# IoT_Shield_v1_0.net
KiCad netlist of a schematic drawn in EAGLE
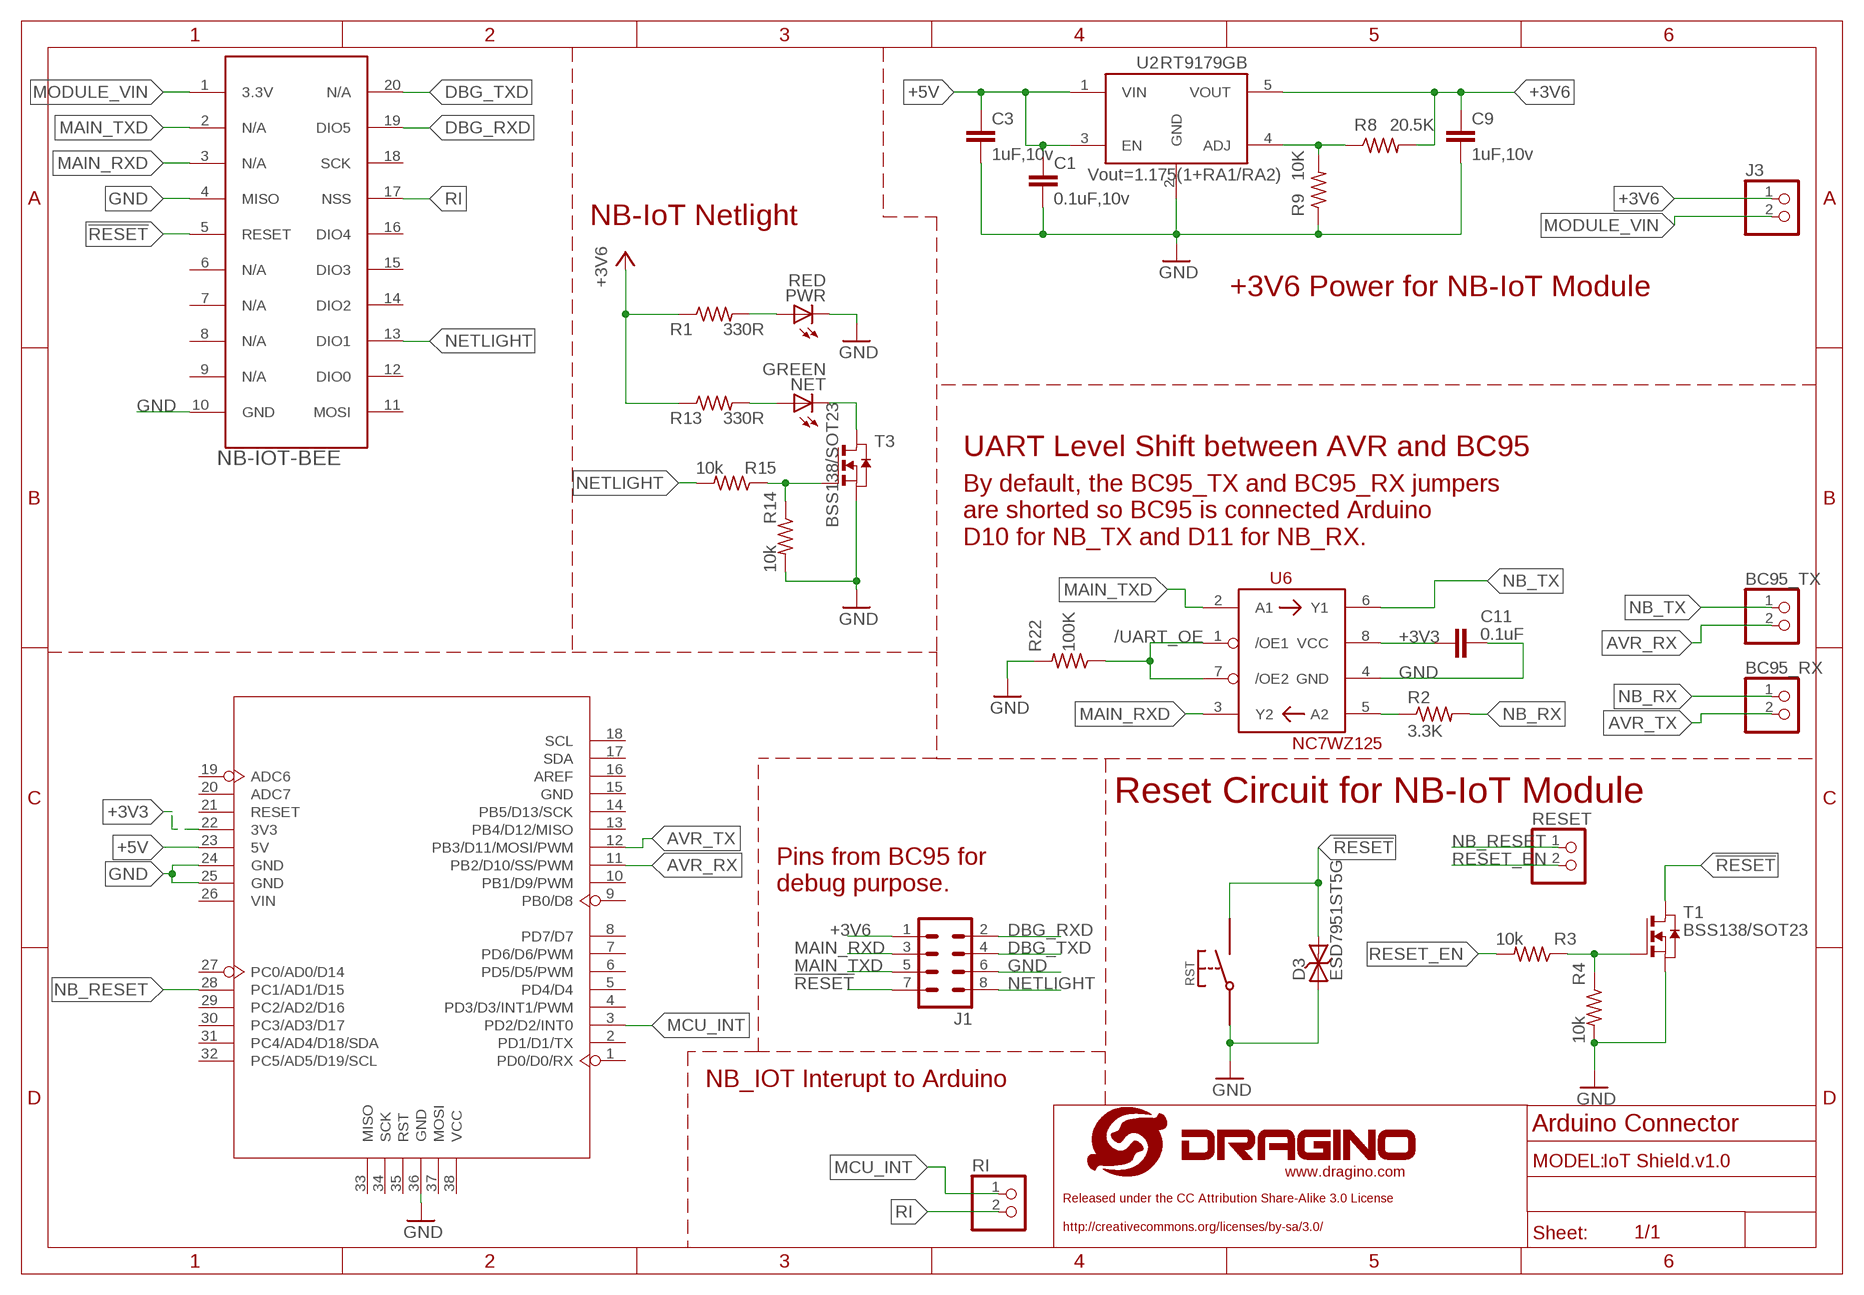
[diagram p0: schematic, sheet 1]

(export (version "E")
  (design (tool "Eeschema 10.0.6"))
  (components
    (comp (ref "BC95_RX")
      (value "PINHD-1X2")
      (footprint "eagle-import:1X02")
      (libsource (lib "eagle-import") (part "PINHD-1X2"))
    )
    (comp (ref "BC95_TX")
      (value "PINHD-1X2")
      (footprint "eagle-import:1X02")
      (libsource (lib "eagle-import") (part "PINHD-1X2"))
    )
    (comp (ref "C1")
      (value "0.1uF,10v")
      (footprint "eagle-import:C0402")
      (libsource (lib "eagle-import") (part "C-EUC0402"))
    )
    (comp (ref "C3")
      (value "1uF,10v")
      (footprint "eagle-import:C0402")
      (libsource (lib "eagle-import") (part "C-EUC0402"))
    )
    (comp (ref "C9")
      (value "1uF,10v")
      (footprint "eagle-import:C0402")
      (libsource (lib "eagle-import") (part "C-EUC0402"))
    )
    (comp (ref "C11")
      (value "0.1uF")
      (footprint "eagle-import:C0402")
      (libsource (lib "eagle-import") (part "C-EUC0402"))
    )
    (comp (ref "D3")
      (value "ESD7951ST5G")
      (footprint "eagle-import:SOD−923")
      (libsource (lib "eagle-import") (part "TVSSOD−923"))
    )
    (comp (ref "IOT-BEE")
      (value "NB-IOT-BEE")
      (footprint "eagle-import:LORA")
      (libsource (lib "eagle-import") (part "LORAHAT_S"))
    )
    (comp (ref "J1")
      (value "MA04-2")
      (footprint "eagle-import:MA04-2")
      (libsource (lib "eagle-import") (part "MA04-2"))
    )
    (comp (ref "J3")
      (value "PINHD-1X2")
      (footprint "eagle-import:1X02")
      (libsource (lib "eagle-import") (part "PINHD-1X2"))
    )
    (comp (ref "NET")
      (value "GREEN")
      (footprint "eagle-import:CHIP-LED0603")
      (libsource (lib "eagle-import") (part "LEDCHIP-LED0603"))
    )
    (comp (ref "PWR")
      (value "RED")
      (footprint "eagle-import:CHIP-LED0603")
      (libsource (lib "eagle-import") (part "LEDCHIP-LED0603"))
    )
    (comp (ref "R1")
      (value "330R")
      (footprint "eagle-import:R0402")
      (libsource (lib "eagle-import") (part "R-US_R0402"))
    )
    (comp (ref "R2")
      (value "3.3K")
      (footprint "eagle-import:R0402")
      (libsource (lib "eagle-import") (part "R-US_R0402"))
    )
    (comp (ref "R3")
      (value "10k")
      (footprint "eagle-import:R0402")
      (libsource (lib "eagle-import") (part "R-US_R0402"))
    )
    (comp (ref "R4")
      (value "10k")
      (footprint "eagle-import:R0402")
      (libsource (lib "eagle-import") (part "R-US_R0402"))
    )
    (comp (ref "R8")
      (value "20.5K")
      (footprint "eagle-import:R0402")
      (libsource (lib "eagle-import") (part "R-US_R0402"))
    )
    (comp (ref "R9")
      (value "10K")
      (footprint "eagle-import:R0402")
      (libsource (lib "eagle-import") (part "R-US_R0402"))
    )
    (comp (ref "R13")
      (value "330R")
      (footprint "eagle-import:R0402")
      (libsource (lib "eagle-import") (part "R-US_R0402"))
    )
    (comp (ref "R14")
      (value "10k")
      (footprint "eagle-import:R0402")
      (libsource (lib "eagle-import") (part "R-US_R0402"))
    )
    (comp (ref "R15")
      (value "10k")
      (footprint "eagle-import:R0402")
      (libsource (lib "eagle-import") (part "R-US_R0402"))
    )
    (comp (ref "R22")
      (value "100K")
      (footprint "eagle-import:R0402")
      (libsource (lib "eagle-import") (part "R-US_R0402"))
    )
    (comp (ref "RESET")
      (value "PINHD-1X2")
      (footprint "eagle-import:1X02")
      (libsource (lib "eagle-import") (part "PINHD-1X2"))
    )
    (comp (ref "RI")
      (value "PINHD-1X2")
      (footprint "eagle-import:1X02")
      (libsource (lib "eagle-import") (part "PINHD-1X2"))
    )
    (comp (ref "RST")
      (value "SWITCHTS-017")
      (footprint "eagle-import:TS-017")
      (libsource (lib "eagle-import") (part "SWITCHTS-017"))
    )
    (comp (ref "T1")
      (value "BSS138/SOT23")
      (footprint "eagle-import:SOT-23")
      (libsource (lib "eagle-import") (part "NMOSFET-SOT23"))
    )
    (comp (ref "T3")
      (value "BSS138/SOT23")
      (footprint "eagle-import:SOT-23")
      (libsource (lib "eagle-import") (part "NMOSFET-SOT23"))
    )
    (comp (ref "U$1")
      (value "LOGO-NEW")
      (footprint "eagle-import:LOGO-SILK-NEW")
      (libsource (lib "eagle-import") (part "LOGO-NEW"))
    )
    (comp (ref "U2")
      (value "RT9179GB")
      (footprint "eagle-import:SOT23-5")
      (libsource (lib "eagle-import") (part "RT9179"))
    )
    (comp (ref "U5")
      (value "MOUDLE_ARDUINO-38PMOUDLE_ARDUINO-38P_L")
      (footprint "eagle-import:MOUDLE_ARDUINO-38P_L")
      (libsource (lib "eagle-import") (part "MOUDLE_ARDUINO-38PMOUDLE_ARDUINO-38P_L"))
    )
    (comp (ref "U6")
      (value "NC7WZ125")
      (footprint "eagle-import:US8")
      (libsource (lib "eagle-import") (part "NC7WZ125"))
    )
  )
  (nets
    (net (code "1") (name "+3V3") (class "Default")
      (node (ref "C11") (pin "2") (pinfunction "2_2") (pintype "passive"))
      (node (ref "U5") (pin "22") (pinfunction "3V3_22") (pintype "bidirectional"))
      (node (ref "U6") (pin "8") (pinfunction "VCC_8") (pintype "power_in"))
    )
    (net (code "2") (name "+3V6") (class "Default")
      (node (ref "C9") (pin "1") (pinfunction "1_1") (pintype "passive"))
      (node (ref "J1") (pin "1") (pinfunction "1_1") (pintype "passive"))
      (node (ref "J3") (pin "1") (pinfunction "1_1") (pintype "passive"))
      (node (ref "R1") (pin "1") (pinfunction "1_1") (pintype "passive"))
      (node (ref "R13") (pin "1") (pinfunction "1_1") (pintype "passive"))
      (node (ref "R8") (pin "2") (pinfunction "2_2") (pintype "passive"))
      (node (ref "U2") (pin "5") (pinfunction "VOUT_5") (pintype "bidirectional"))
    )
    (net (code "3") (name "+5V") (class "Default")
      (node (ref "C1") (pin "1") (pinfunction "1_1") (pintype "passive"))
      (node (ref "C3") (pin "1") (pinfunction "1_1") (pintype "passive"))
      (node (ref "U2") (pin "1") (pinfunction "VIN_1") (pintype "bidirectional"))
      (node (ref "U2") (pin "3") (pinfunction "EN_3") (pintype "bidirectional"))
      (node (ref "U5") (pin "23") (pinfunction "5V_23") (pintype "bidirectional"))
    )
    (net (code "4") (name "/{slash}UART_OE") (class "Default")
      (node (ref "R22") (pin "1") (pinfunction "1_1") (pintype "passive"))
      (node (ref "U6") (pin "1") (pinfunction "/OE1_1") (pintype "input"))
      (node (ref "U6") (pin "7") (pinfunction "/OE2_7") (pintype "input"))
    )
    (net (code "5") (name "/~{RESET}") (class "Default")
      (node (ref "D3") (pin "P$2") (pinfunction "2_P$2") (pintype "passive"))
      (node (ref "IOT-BEE") (pin "5") (pinfunction "RESET_5") (pintype "bidirectional"))
      (node (ref "J1") (pin "7") (pinfunction "7_7") (pintype "passive"))
      (node (ref "RST") (pin "P$2") (pinfunction "P$2_P$2") (pintype "bidirectional"))
      (node (ref "T1") (pin "1") (pinfunction "D_1") (pintype "passive"))
    )
    (net (code "6") (name "AVR_RX") (class "Default")
      (node (ref "BC95_TX") (pin "2") (pinfunction "2_2") (pintype "passive"))
      (node (ref "U5") (pin "11") (pinfunction "PB2/D10/SS/PWM_11") (pintype "bidirectional"))
    )
    (net (code "7") (name "AVR_TX") (class "Default")
      (node (ref "BC95_RX") (pin "2") (pinfunction "2_2") (pintype "passive"))
      (node (ref "U5") (pin "12") (pinfunction "PB3/D11/MOSI/PWM_12") (pintype "bidirectional"))
    )
    (net (code "8") (name "DBG_RXD") (class "Default")
      (node (ref "IOT-BEE") (pin "19") (pinfunction "DIO5_19") (pintype "bidirectional"))
      (node (ref "J1") (pin "2") (pinfunction "2_2") (pintype "passive"))
    )
    (net (code "9") (name "DBG_TXD") (class "Default")
      (node (ref "IOT-BEE") (pin "20") (pinfunction "N/A_20") (pintype "bidirectional"))
      (node (ref "J1") (pin "4") (pinfunction "4_4") (pintype "passive"))
    )
    (net (code "10") (name "GND") (class "Default")
      (node (ref "C1") (pin "2") (pinfunction "2_2") (pintype "passive"))
      (node (ref "C11") (pin "1") (pinfunction "1_1") (pintype "passive"))
      (node (ref "C3") (pin "2") (pinfunction "2_2") (pintype "passive"))
      (node (ref "C9") (pin "2") (pinfunction "2_2") (pintype "passive"))
      (node (ref "D3") (pin "P$1") (pinfunction "1_P$1") (pintype "passive"))
      (node (ref "IOT-BEE") (pin "10") (pinfunction "GND_10") (pintype "bidirectional"))
      (node (ref "IOT-BEE") (pin "4") (pinfunction "MISO_4") (pintype "bidirectional"))
      (node (ref "J1") (pin "6") (pinfunction "6_6") (pintype "passive"))
      (node (ref "PWR") (pin "C") (pinfunction "C_C") (pintype "passive"))
      (node (ref "R14") (pin "2") (pinfunction "2_2") (pintype "passive"))
      (node (ref "R22") (pin "2") (pinfunction "2_2") (pintype "passive"))
      (node (ref "R4") (pin "2") (pinfunction "2_2") (pintype "passive"))
      (node (ref "R9") (pin "1") (pinfunction "1_1") (pintype "passive"))
      (node (ref "RST") (pin "P$1") (pinfunction "P$1_P$1") (pintype "bidirectional"))
      (node (ref "T1") (pin "2") (pinfunction "S_2") (pintype "passive"))
      (node (ref "T3") (pin "2") (pinfunction "S_2") (pintype "passive"))
      (node (ref "U2") (pin "2") (pinfunction "GND_2") (pintype "bidirectional"))
      (node (ref "U5") (pin "24") (pinfunction "GND_24") (pintype "bidirectional"))
      (node (ref "U5") (pin "25") (pinfunction "GND_25") (pintype "bidirectional"))
      (node (ref "U5") (pin "36") (pinfunction "GND_36") (pintype "bidirectional"))
      (node (ref "U6") (pin "4") (pinfunction "GND_4") (pintype "power_in"))
    )
    (net (code "11") (name "MAIN_RXD") (class "Default")
      (node (ref "IOT-BEE") (pin "3") (pinfunction "N/A_3") (pintype "bidirectional"))
      (node (ref "J1") (pin "3") (pinfunction "3_3") (pintype "passive"))
      (node (ref "U6") (pin "3") (pinfunction "Y2_3") (pintype "output"))
    )
    (net (code "12") (name "MAIN_TXD") (class "Default")
      (node (ref "IOT-BEE") (pin "2") (pinfunction "N/A_2") (pintype "bidirectional"))
      (node (ref "J1") (pin "5") (pinfunction "5_5") (pintype "passive"))
      (node (ref "U6") (pin "2") (pinfunction "A1_2") (pintype "input"))
    )
    (net (code "13") (name "MCU_INT") (class "Default")
      (node (ref "RI") (pin "1") (pinfunction "1_1") (pintype "passive"))
      (node (ref "U5") (pin "3") (pinfunction "PD2/D2/INT0_3") (pintype "bidirectional"))
    )
    (net (code "14") (name "MODULE_VIN") (class "Default")
      (node (ref "IOT-BEE") (pin "1") (pinfunction "3.3V_1") (pintype "bidirectional"))
      (node (ref "J3") (pin "2") (pinfunction "2_2") (pintype "passive"))
    )
    (net (code "15") (name "NB_RESET") (class "Default")
      (node (ref "RESET") (pin "1") (pinfunction "1_1") (pintype "passive"))
      (node (ref "U5") (pin "28") (pinfunction "PC1/AD1/D15_28") (pintype "bidirectional"))
    )
    (net (code "16") (name "NB_RX") (class "Default")
      (node (ref "BC95_RX") (pin "1") (pinfunction "1_1") (pintype "passive"))
      (node (ref "R2") (pin "2") (pinfunction "2_2") (pintype "passive"))
    )
    (net (code "17") (name "NB_TX") (class "Default")
      (node (ref "BC95_TX") (pin "1") (pinfunction "1_1") (pintype "passive"))
      (node (ref "U6") (pin "6") (pinfunction "Y1_6") (pintype "output"))
    )
    (net (code "18") (name "NETLIGHT") (class "Default")
      (node (ref "IOT-BEE") (pin "13") (pinfunction "DIO1_13") (pintype "bidirectional"))
      (node (ref "J1") (pin "8") (pinfunction "8_8") (pintype "passive"))
      (node (ref "R15") (pin "2") (pinfunction "2_2") (pintype "passive"))
    )
    (net (code "19") (name "Net-(NET-PadA)") (class "Default")
      (node (ref "NET") (pin "A") (pinfunction "A_A") (pintype "passive"))
      (node (ref "R13") (pin "2") (pinfunction "2_2") (pintype "passive"))
    )
    (net (code "20") (name "Net-(PWR-PadA)") (class "Default")
      (node (ref "PWR") (pin "A") (pinfunction "A_A") (pintype "passive"))
      (node (ref "R1") (pin "2") (pinfunction "2_2") (pintype "passive"))
    )
    (net (code "21") (name "Net-(T1-G)") (class "Default")
      (node (ref "R3") (pin "1") (pinfunction "1_1") (pintype "passive"))
      (node (ref "R4") (pin "1") (pinfunction "1_1") (pintype "passive"))
      (node (ref "T1") (pin "3") (pinfunction "G_3") (pintype "passive"))
    )
    (net (code "22") (name "Net-(T3-D)") (class "Default")
      (node (ref "NET") (pin "C") (pinfunction "C_C") (pintype "passive"))
      (node (ref "T3") (pin "1") (pinfunction "D_1") (pintype "passive"))
    )
    (net (code "23") (name "Net-(T3-G)") (class "Default")
      (node (ref "R14") (pin "1") (pinfunction "1_1") (pintype "passive"))
      (node (ref "R15") (pin "1") (pinfunction "1_1") (pintype "passive"))
      (node (ref "T3") (pin "3") (pinfunction "G_3") (pintype "passive"))
    )
    (net (code "24") (name "Net-(U2-ADJ)") (class "Default")
      (node (ref "R8") (pin "1") (pinfunction "1_1") (pintype "passive"))
      (node (ref "R9") (pin "2") (pinfunction "2_2") (pintype "passive"))
      (node (ref "U2") (pin "4") (pinfunction "ADJ_4") (pintype "bidirectional"))
    )
    (net (code "25") (name "Net-(U6-A2)") (class "Default")
      (node (ref "R2") (pin "1") (pinfunction "1_1") (pintype "passive"))
      (node (ref "U6") (pin "5") (pinfunction "A2_5") (pintype "input"))
    )
    (net (code "26") (name "RESET_EN") (class "Default")
      (node (ref "R3") (pin "2") (pinfunction "2_2") (pintype "passive"))
      (node (ref "RESET") (pin "2") (pinfunction "2_2") (pintype "passive"))
    )
    (net (code "27") (name "RI") (class "Default")
      (node (ref "IOT-BEE") (pin "17") (pinfunction "NSS_17") (pintype "bidirectional"))
      (node (ref "RI") (pin "2") (pinfunction "2_2") (pintype "passive"))
    )
    (net (code "28") (name "unconnected-(IOT-BEE-DIO0-Pad12)") (class "Default")
      (node (ref "IOT-BEE") (pin "12") (pinfunction "DIO0_12") (pintype "bidirectional"))
    )
    (net (code "29") (name "unconnected-(IOT-BEE-DIO2-Pad14)") (class "Default")
      (node (ref "IOT-BEE") (pin "14") (pinfunction "DIO2_14") (pintype "bidirectional"))
    )
    (net (code "30") (name "unconnected-(IOT-BEE-DIO3-Pad15)") (class "Default")
      (node (ref "IOT-BEE") (pin "15") (pinfunction "DIO3_15") (pintype "bidirectional"))
    )
    (net (code "31") (name "unconnected-(IOT-BEE-DIO4-Pad16)") (class "Default")
      (node (ref "IOT-BEE") (pin "16") (pinfunction "DIO4_16") (pintype "bidirectional"))
    )
    (net (code "32") (name "unconnected-(IOT-BEE-MOSI-Pad11)") (class "Default")
      (node (ref "IOT-BEE") (pin "11") (pinfunction "MOSI_11") (pintype "bidirectional"))
    )
    (net (code "33") (name "unconnected-(IOT-BEE-N{slash}A-Pad6)") (class "Default")
      (node (ref "IOT-BEE") (pin "6") (pinfunction "N/A_6") (pintype "bidirectional"))
    )
    (net (code "34") (name "unconnected-(IOT-BEE-N{slash}A-Pad7)") (class "Default")
      (node (ref "IOT-BEE") (pin "7") (pinfunction "N/A_7") (pintype "bidirectional"))
    )
    (net (code "35") (name "unconnected-(IOT-BEE-N{slash}A-Pad8)") (class "Default")
      (node (ref "IOT-BEE") (pin "8") (pinfunction "N/A_8") (pintype "bidirectional"))
    )
    (net (code "36") (name "unconnected-(IOT-BEE-N{slash}A-Pad9)") (class "Default")
      (node (ref "IOT-BEE") (pin "9") (pinfunction "N/A_9") (pintype "bidirectional"))
    )
    (net (code "37") (name "unconnected-(IOT-BEE-SCK-Pad18)") (class "Default")
      (node (ref "IOT-BEE") (pin "18") (pinfunction "SCK_18") (pintype "bidirectional"))
    )
    (net (code "38") (name "unconnected-(U5-ADC6-Pad19)") (class "Default")
      (node (ref "U5") (pin "19") (pinfunction "ADC6_19") (pintype "bidirectional"))
    )
    (net (code "39") (name "unconnected-(U5-ADC7-Pad20)") (class "Default")
      (node (ref "U5") (pin "20") (pinfunction "ADC7_20") (pintype "bidirectional"))
    )
    (net (code "40") (name "unconnected-(U5-AREF-Pad16)") (class "Default")
      (node (ref "U5") (pin "16") (pinfunction "AREF_16") (pintype "bidirectional"))
    )
    (net (code "41") (name "unconnected-(U5-GND-Pad15)") (class "Default")
      (node (ref "U5") (pin "15") (pinfunction "GND_15") (pintype "bidirectional"))
    )
    (net (code "42") (name "unconnected-(U5-MISO-Pad33)") (class "Default")
      (node (ref "U5") (pin "33") (pinfunction "MISO_33") (pintype "bidirectional"))
    )
    (net (code "43") (name "unconnected-(U5-MOSI-Pad37)") (class "Default")
      (node (ref "U5") (pin "37") (pinfunction "MOSI_37") (pintype "bidirectional"))
    )
    (net (code "44") (name "unconnected-(U5-PB0{slash}D8-Pad9)") (class "Default")
      (node (ref "U5") (pin "9") (pinfunction "PB0/D8_9") (pintype "bidirectional"))
    )
    (net (code "45") (name "unconnected-(U5-PB1{slash}D9{slash}PWM-Pad10)") (class "Default")
      (node (ref "U5") (pin "10") (pinfunction "PB1/D9/PWM_10") (pintype "bidirectional"))
    )
    (net (code "46") (name "unconnected-(U5-PB4{slash}D12{slash}MISO-Pad13)") (class "Default")
      (node (ref "U5") (pin "13") (pinfunction "PB4/D12/MISO_13") (pintype "bidirectional"))
    )
    (net (code "47") (name "unconnected-(U5-PB5{slash}D13{slash}SCK-Pad14)") (class "Default")
      (node (ref "U5") (pin "14") (pinfunction "PB5/D13/SCK_14") (pintype "bidirectional"))
    )
    (net (code "48") (name "unconnected-(U5-PC0{slash}AD0{slash}D14-Pad27)") (class "Default")
      (node (ref "U5") (pin "27") (pinfunction "PC0/AD0/D14_27") (pintype "bidirectional"))
    )
    (net (code "49") (name "unconnected-(U5-PC2{slash}AD2{slash}D16-Pad29)") (class "Default")
      (node (ref "U5") (pin "29") (pinfunction "PC2/AD2/D16_29") (pintype "bidirectional"))
    )
    (net (code "50") (name "unconnected-(U5-PC3{slash}AD3{slash}D17-Pad30)") (class "Default")
      (node (ref "U5") (pin "30") (pinfunction "PC3/AD3/D17_30") (pintype "bidirectional"))
    )
    (net (code "51") (name "unconnected-(U5-PC4{slash}AD4{slash}D18{slash}SDA-Pad31)") (class "Default")
      (node (ref "U5") (pin "31") (pinfunction "PC4/AD4/D18/SDA_31") (pintype "bidirectional"))
    )
    (net (code "52") (name "unconnected-(U5-PC5{slash}AD5{slash}D19{slash}SCL-Pad32)") (class "Default")
      (node (ref "U5") (pin "32") (pinfunction "PC5/AD5/D19/SCL_32") (pintype "bidirectional"))
    )
    (net (code "53") (name "unconnected-(U5-PD0{slash}D0{slash}RX-Pad1)") (class "Default")
      (node (ref "U5") (pin "1") (pinfunction "PD0/D0/RX_1") (pintype "bidirectional"))
    )
    (net (code "54") (name "unconnected-(U5-PD1{slash}D1{slash}TX-Pad2)") (class "Default")
      (node (ref "U5") (pin "2") (pinfunction "PD1/D1/TX_2") (pintype "bidirectional"))
    )
    (net (code "55") (name "unconnected-(U5-PD3{slash}D3{slash}INT1{slash}PWM-Pad4)") (class "Default")
      (node (ref "U5") (pin "4") (pinfunction "PD3/D3/INT1/PWM_4") (pintype "bidirectional"))
    )
    (net (code "56") (name "unconnected-(U5-PD4{slash}D4-Pad5)") (class "Default")
      (node (ref "U5") (pin "5") (pinfunction "PD4/D4_5") (pintype "bidirectional"))
    )
    (net (code "57") (name "unconnected-(U5-PD5{slash}D5{slash}PWM-Pad6)") (class "Default")
      (node (ref "U5") (pin "6") (pinfunction "PD5/D5/PWM_6") (pintype "bidirectional"))
    )
    (net (code "58") (name "unconnected-(U5-PD6{slash}D6{slash}PWM-Pad7)") (class "Default")
      (node (ref "U5") (pin "7") (pinfunction "PD6/D6/PWM_7") (pintype "bidirectional"))
    )
    (net (code "59") (name "unconnected-(U5-PD7{slash}D7-Pad8)") (class "Default")
      (node (ref "U5") (pin "8") (pinfunction "PD7/D7_8") (pintype "bidirectional"))
    )
    (net (code "60") (name "unconnected-(U5-RESET-Pad21)") (class "Default")
      (node (ref "U5") (pin "21") (pinfunction "RESET_21") (pintype "bidirectional"))
    )
    (net (code "61") (name "unconnected-(U5-RST-Pad35)") (class "Default")
      (node (ref "U5") (pin "35") (pinfunction "RST_35") (pintype "bidirectional"))
    )
    (net (code "62") (name "unconnected-(U5-SCK-Pad34)") (class "Default")
      (node (ref "U5") (pin "34") (pinfunction "SCK_34") (pintype "bidirectional"))
    )
    (net (code "63") (name "unconnected-(U5-SCL-Pad18)") (class "Default")
      (node (ref "U5") (pin "18") (pinfunction "SCL_18") (pintype "bidirectional"))
    )
    (net (code "64") (name "unconnected-(U5-SDA-Pad17)") (class "Default")
      (node (ref "U5") (pin "17") (pinfunction "SDA_17") (pintype "bidirectional"))
    )
    (net (code "65") (name "unconnected-(U5-VCC-Pad38)") (class "Default")
      (node (ref "U5") (pin "38") (pinfunction "VCC_38") (pintype "bidirectional"))
    )
    (net (code "66") (name "unconnected-(U5-VIN-Pad26)") (class "Default")
      (node (ref "U5") (pin "26") (pinfunction "VIN_26") (pintype "bidirectional"))
    )
  )
)
